# ESP_Clock_v3_1.net
KiCad netlist of a schematic drawn in EAGLE
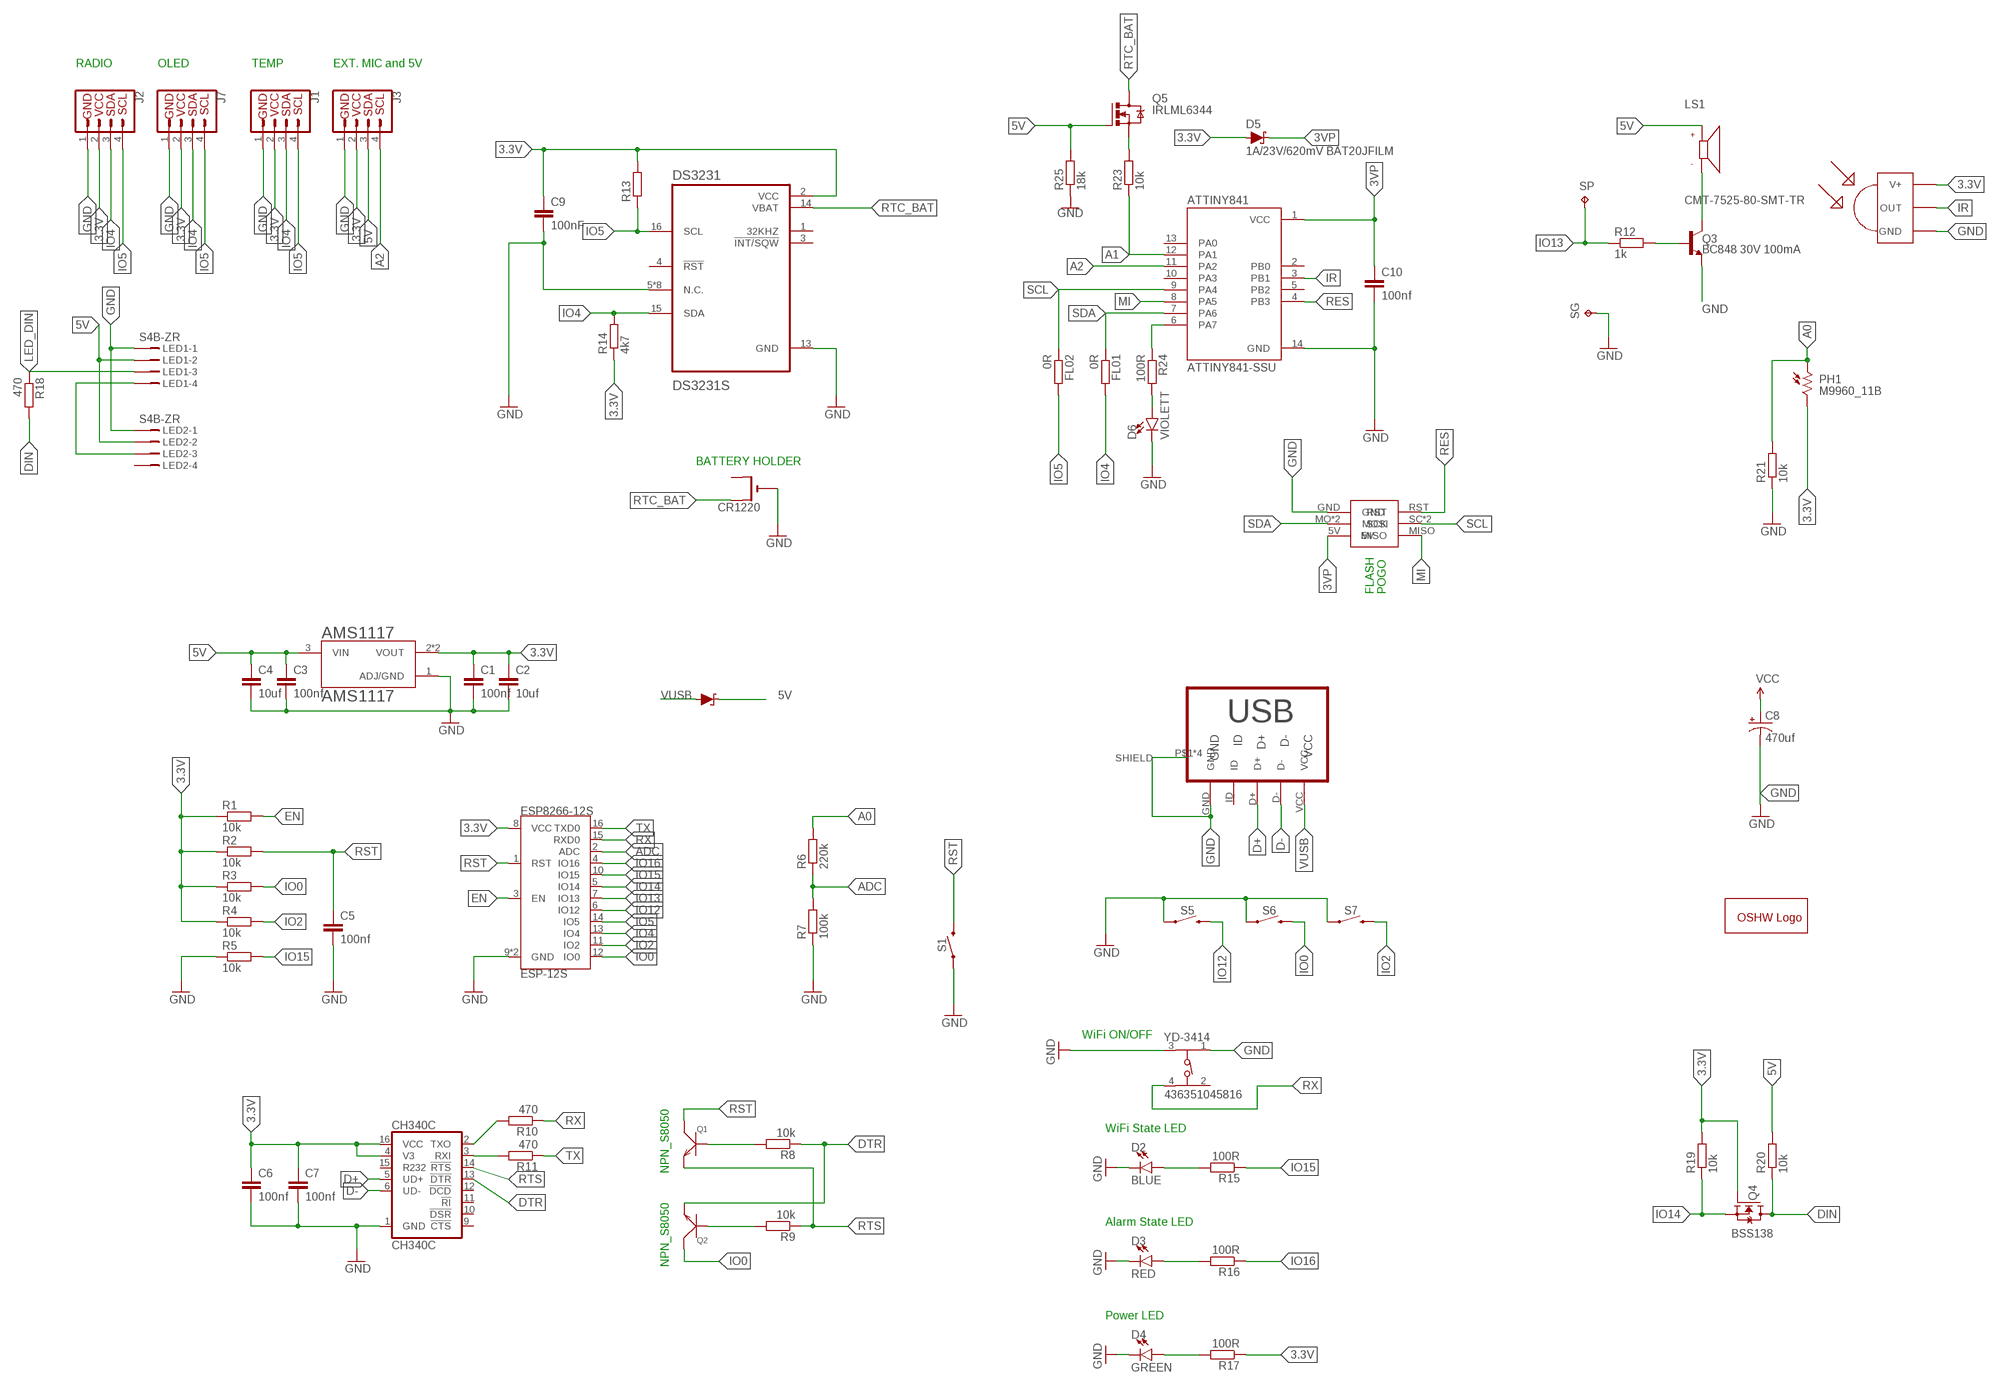
[diagram p0: schematic, sheet 1]

(export (version "E")
  (design (tool "Eeschema 10.0.6"))
  (components
    (comp (ref "AMS1117")
      (value "AMS1117")
      (footprint "eagle-import:SOT229P700X180-4N")
      (fields (field (name "MF") "Advanced Monolithic Systems"))
      (libsource (lib "eagle-import") (part "AMS1117"))
    )
    (comp (ref "ATTINY841")
      (value "ATTINY841-SSU")
      (footprint "eagle-import:SOIC127P599X175-14N")
      (fields (field (name "MF") "Microchip"))
      (libsource (lib "eagle-import") (part "ATTINY841-SSU"))
    )
    (comp (ref "C1")
      (value "100nf")
      (footprint "eagle-import:C0603")
      (libsource (lib "eagle-import") (part "C-EUC0603"))
    )
    (comp (ref "C2")
      (value "10uf")
      (footprint "eagle-import:C0805")
      (libsource (lib "eagle-import") (part "C-EUC0805"))
    )
    (comp (ref "C3")
      (value "100nf")
      (footprint "eagle-import:C0603")
      (libsource (lib "eagle-import") (part "C-EUC0603"))
    )
    (comp (ref "C4")
      (value "10uf")
      (footprint "eagle-import:C0805")
      (libsource (lib "eagle-import") (part "C-EUC0805"))
    )
    (comp (ref "C5")
      (value "100nf")
      (footprint "eagle-import:C0603")
      (libsource (lib "eagle-import") (part "C-EUC0603"))
    )
    (comp (ref "C6")
      (value "100nf")
      (footprint "eagle-import:C0603")
      (libsource (lib "eagle-import") (part "C-EUC0603"))
    )
    (comp (ref "C7")
      (value "100nf")
      (footprint "eagle-import:C0603")
      (libsource (lib "eagle-import") (part "C-EUC0603"))
    )
    (comp (ref "C8")
      (value "470uf")
      (footprint "eagle-import:EIA7343")
      (libsource (lib "eagle-import") (part "CAP_POL7343"))
    )
    (comp (ref "C9")
      (value "100nF")
      (footprint "eagle-import:C0603")
      (libsource (lib "eagle-import") (part "C-EUC0603"))
    )
    (comp (ref "C10")
      (value "100nf")
      (footprint "eagle-import:C0603")
      (libsource (lib "eagle-import") (part "C-EUC0603"))
    )
    (comp (ref "CH340C")
      (value "CH340C")
      (footprint "eagle-import:SO016")
      (fields (field (name "MF") "WCH"))
      (libsource (lib "eagle-import") (part "CH340C"))
    )
    (comp (ref "CR1220")
      (value "CR1220SMT")
      (footprint "eagle-import:CR1220-SMD")
      (libsource (lib "eagle-import") (part "CR1220SMT"))
    )
    (comp (ref "D1")
      (value "MBR130T1G, SL; SOD123 or SMA, 1A")
      (footprint "eagle-import:SMA-DIODE")
      (libsource (lib "eagle-import") (part "DIODE-SCHOTTKY-B340A"))
    )
    (comp (ref "D2")
      (value "BLUE")
      (footprint "eagle-import:LED-0603")
      (libsource (lib "eagle-import") (part "LED-BLUE0603"))
    )
    (comp (ref "D3")
      (value "RED")
      (footprint "eagle-import:LED-0603")
      (libsource (lib "eagle-import") (part "LED-BLUE0603"))
    )
    (comp (ref "D4")
      (value "GREEN")
      (footprint "eagle-import:LED-0603")
      (libsource (lib "eagle-import") (part "LED-BLUE0603"))
    )
    (comp (ref "D5")
      (value "1A/23V/620mV BAT20JFILM")
      (footprint "eagle-import:SOD-323")
      (libsource (lib "eagle-import") (part "DIODE-SCHOTTKY-BAT20J"))
    )
    (comp (ref "D6")
      (value "VIOLETT")
      (footprint "eagle-import:LED-0603")
      (libsource (lib "eagle-import") (part "LED-BLUE0603"))
    )
    (comp (ref "DS3231")
      (value "DS3231S")
      (footprint "eagle-import:SOIC127P1032X265-16N")
      (fields (field (name "MF") "Maxim Integrated"))
      (libsource (lib "eagle-import") (part "DS3231S"))
    )
    (comp (ref "ESP8266-12S")
      (value "ESP-12S")
      (footprint "eagle-import:ESP-12S")
      (fields (field (name "MF") "RF Solutions"))
      (libsource (lib "eagle-import") (part "ESP-12S"))
    )
    (comp (ref "FL01")
      (value "0R")
      (footprint "eagle-import:R0603")
      (libsource (lib "eagle-import") (part "R-EU_R0603"))
    )
    (comp (ref "FL02")
      (value "0R")
      (footprint "eagle-import:R0603")
      (libsource (lib "eagle-import") (part "R-EU_R0603"))
    )
    (comp (ref "GOLD_ORB_SM1")
      (value "OSHWLOGOLOGO5MM")
      (footprint "eagle-import:OSHW_5MM")
      (libsource (lib "eagle-import") (part "OSHWLOGOLOGO5MM"))
    )
    (comp (ref "J1")
      (value "QWIIC_CONNECTORJS-1MM")
      (footprint "eagle-import:1X04_1MM_RA")
      (libsource (lib "eagle-import") (part "QWIIC_CONNECTORJS-1MM"))
    )
    (comp (ref "J2")
      (value "QWIIC_CONNECTORJS-1MM")
      (footprint "eagle-import:1X04_1MM_RA")
      (libsource (lib "eagle-import") (part "QWIIC_CONNECTORJS-1MM"))
    )
    (comp (ref "J3")
      (value "QWIIC_CONNECTORJS-1MM")
      (footprint "eagle-import:1X04_1MM_RA")
      (libsource (lib "eagle-import") (part "QWIIC_CONNECTORJS-1MM"))
    )
    (comp (ref "J7")
      (value "QWIIC_CONNECTORJS-1MM")
      (footprint "eagle-import:1X04_1MM_RA")
      (libsource (lib "eagle-import") (part "QWIIC_CONNECTORJS-1MM"))
    )
    (comp (ref "LED1")
      (value "S4B-ZR")
      (footprint "eagle-import:S4B-ZR")
      (fields (field (name "MF") "FARNELL") (field (name "MPN") "S4B-ZR(LF)(SN)"))
      (libsource (lib "eagle-import") (part "?4B-ZRS"))
    )
    (comp (ref "LED2")
      (value "S4B-ZR")
      (footprint "eagle-import:S4B-ZR")
      (fields (field (name "MF") "FARNELL") (field (name "MPN") "S4B-ZR(LF)(SN)"))
      (libsource (lib "eagle-import") (part "?4B-ZRS"))
    )
    (comp (ref "LS1")
      (value "CMT-7525-80-SMT-TR")
      (footprint "eagle-import:XDCR_CMT-7525-80-SMT-TR")
      (fields (field (name "MF") "CUI Devices"))
      (libsource (lib "eagle-import") (part "CMT-7525-80-SMT-TR"))
    )
    (comp (ref "MICRO-USB")
      (value "MICRO-USB-B")
      (footprint "eagle-import:MICRO_USB_4_LEGS")
      (libsource (lib "eagle-import") (part "MICRO-USB-B"))
    )
    (comp (ref "PH1")
      (value "M9960_11B")
      (footprint "eagle-import:M9960")
      (libsource (lib "eagle-import") (part "M9960_11B"))
    )
    (comp (ref "Q1")
      (value "NPN_S8050")
      (footprint "eagle-import:SOT-23")
      (fields (field (name "MF") "Microdiode Electronics") (field (name "MP") "S8050"))
      (libsource (lib "eagle-import") (part "SMD-TRANSISTORS-NPN-25V-500MW(SOT-23)"))
    )
    (comp (ref "Q2")
      (value "NPN_S8050")
      (footprint "eagle-import:SOT-23")
      (fields (field (name "MF") "Microdiode Electronics") (field (name "MP") "S8050"))
      (libsource (lib "eagle-import") (part "SMD-TRANSISTORS-NPN-25V-500MW(SOT-23)"))
    )
    (comp (ref "Q3")
      (value "BC848 30V 100mA")
      (footprint "eagle-import:SOT23-3")
      (libsource (lib "eagle-import") (part "TRANS_NPN-MMBT2222AL"))
    )
    (comp (ref "Q4")
      (value "BSS138")
      (footprint "eagle-import:SOT95P240X111-3N")
      (fields (field (name "MF") "ON Semiconductor"))
      (libsource (lib "eagle-import") (part "BSS138"))
    )
    (comp (ref "Q5")
      (value "IRLML6344")
      (footprint "eagle-import:SOT23")
      (fields (field (name "MF") "Infineon Technologies"))
      (libsource (lib "eagle-import") (part "IRLML6344"))
    )
    (comp (ref "R1")
      (value "10k")
      (footprint "eagle-import:R0603")
      (libsource (lib "eagle-import") (part "resistor_348_R-EU_R0603"))
    )
    (comp (ref "R2")
      (value "10k")
      (footprint "eagle-import:R0603")
      (libsource (lib "eagle-import") (part "resistor_348_R-EU_R0603"))
    )
    (comp (ref "R3")
      (value "10k")
      (footprint "eagle-import:R0603")
      (libsource (lib "eagle-import") (part "resistor_348_R-EU_R0603"))
    )
    (comp (ref "R4")
      (value "10k")
      (footprint "eagle-import:R0603")
      (libsource (lib "eagle-import") (part "resistor_348_R-EU_R0603"))
    )
    (comp (ref "R5")
      (value "10k")
      (footprint "eagle-import:R0603")
      (libsource (lib "eagle-import") (part "resistor_348_R-EU_R0603"))
    )
    (comp (ref "R6")
      (value "220k")
      (footprint "eagle-import:R0603")
      (libsource (lib "eagle-import") (part "resistor_348_R-EU_R0603"))
    )
    (comp (ref "R7")
      (value "100k")
      (footprint "eagle-import:R0603")
      (libsource (lib "eagle-import") (part "resistor_348_R-EU_R0603"))
    )
    (comp (ref "R8")
      (value "10k")
      (footprint "eagle-import:R0603")
      (libsource (lib "eagle-import") (part "resistor_348_R-EU_R0603"))
    )
    (comp (ref "R9")
      (value "10k")
      (footprint "eagle-import:R0603")
      (libsource (lib "eagle-import") (part "resistor_348_R-EU_R0603"))
    )
    (comp (ref "R10")
      (value "470")
      (footprint "eagle-import:R0603")
      (libsource (lib "eagle-import") (part "resistor_348_R-EU_R0603"))
    )
    (comp (ref "R11")
      (value "470")
      (footprint "eagle-import:R0603")
      (libsource (lib "eagle-import") (part "resistor_348_R-EU_R0603"))
    )
    (comp (ref "R12")
      (value "1k")
      (footprint "eagle-import:R0603")
      (libsource (lib "eagle-import") (part "R-EU_R0603"))
    )
    (comp (ref "R13")
      (value "4k7")
      (footprint "eagle-import:R0603")
      (libsource (lib "eagle-import") (part "resistor_348_R-EU_R0603"))
    )
    (comp (ref "R14")
      (value "4k7")
      (footprint "eagle-import:R0603")
      (libsource (lib "eagle-import") (part "resistor_348_R-EU_R0603"))
    )
    (comp (ref "R15")
      (value "100R")
      (footprint "eagle-import:R0603")
      (libsource (lib "eagle-import") (part "resistor_348_R-EU_R0603"))
    )
    (comp (ref "R16")
      (value "100R")
      (footprint "eagle-import:R0603")
      (libsource (lib "eagle-import") (part "resistor_348_R-EU_R0603"))
    )
    (comp (ref "R17")
      (value "100R")
      (footprint "eagle-import:R0603")
      (libsource (lib "eagle-import") (part "resistor_348_R-EU_R0603"))
    )
    (comp (ref "R18")
      (value "470")
      (footprint "eagle-import:R0603")
      (libsource (lib "eagle-import") (part "resistor_348_R-EU_R0603"))
    )
    (comp (ref "R19")
      (value "10k")
      (footprint "eagle-import:R0603")
      (libsource (lib "eagle-import") (part "resistor_348_R-EU_R0603"))
    )
    (comp (ref "R20")
      (value "10k")
      (footprint "eagle-import:R0603")
      (libsource (lib "eagle-import") (part "resistor_348_R-EU_R0603"))
    )
    (comp (ref "R21")
      (value "10k")
      (footprint "eagle-import:R0603")
      (libsource (lib "eagle-import") (part "R-EU_R0603"))
    )
    (comp (ref "R23")
      (value "10k")
      (footprint "eagle-import:R0603")
      (libsource (lib "eagle-import") (part "R-EU_R0603"))
    )
    (comp (ref "R24")
      (value "100R")
      (footprint "eagle-import:R0603")
      (libsource (lib "eagle-import") (part "R-EU_R0603"))
    )
    (comp (ref "R25")
      (value "18k")
      (footprint "eagle-import:R0603")
      (libsource (lib "eagle-import") (part "resistor_348_R-EU_R0603"))
    )
    (comp (ref "S1")
      (value "MOMENTARY-SWITCH-SPST-SMD-4.6X2.8MM")
      (footprint "eagle-import:TACTILE_SWITCH_SMD_4.6X2.8MM")
      (libsource (lib "eagle-import") (part "MOMENTARY-SWITCH-SPST-SMD-4.6X2.8MM"))
    )
    (comp (ref "S5")
      (value "MOMENTARY-SWITCH-SPST-SMD-4.6X2.8MM")
      (footprint "eagle-import:TACTILE_SWITCH_SMD_4.6X2.8MM")
      (libsource (lib "eagle-import") (part "MOMENTARY-SWITCH-SPST-SMD-4.6X2.8MM"))
    )
    (comp (ref "S6")
      (value "MOMENTARY-SWITCH-SPST-SMD-4.6X2.8MM")
      (footprint "eagle-import:TACTILE_SWITCH_SMD_4.6X2.8MM")
      (libsource (lib "eagle-import") (part "MOMENTARY-SWITCH-SPST-SMD-4.6X2.8MM"))
    )
    (comp (ref "S7")
      (value "MOMENTARY-SWITCH-SPST-SMD-4.6X2.8MM")
      (footprint "eagle-import:TACTILE_SWITCH_SMD_4.6X2.8MM")
      (libsource (lib "eagle-import") (part "MOMENTARY-SWITCH-SPST-SMD-4.6X2.8MM"))
    )
    (comp (ref "SG")
      (value "TPB1,27")
      (footprint "eagle-import:B1,27")
      (libsource (lib "eagle-import") (part "TPB1,27"))
    )
    (comp (ref "SP")
      (value "TPB1,27")
      (footprint "eagle-import:B1,27")
      (libsource (lib "eagle-import") (part "TPB1,27"))
    )
    (comp (ref "U$1")
      (value "ISCP_PORTPOGONEW")
      (footprint "eagle-import:ISCP_PADS_2ROW2HNEW")
      (libsource (lib "eagle-import") (part "ISCP_PORTPOGONEW"))
    )
    (comp (ref "U$2")
      (value "TSOP4838")
      (footprint "eagle-import:TSOP18XX")
      (fields (field (name "MF") "Vishay"))
      (libsource (lib "eagle-import") (part "TSOP4838"))
    )
    (comp (ref "YD-3414")
      (value "436351045816")
      (footprint "eagle-import:4363X10458XX")
      (libsource (lib "eagle-import") (part "436351045816"))
    )
  )
  (nets
    (net (code "1") (name "3.3V") (class "Default")
      (node (ref "AMS1117") (pin "2") (pinfunction "VOUT_2") (pintype "output"))
      (node (ref "AMS1117") (pin "4") (pinfunction "VOUT_4") (pintype "output"))
      (node (ref "C1") (pin "1") (pinfunction "1_1") (pintype "passive"))
      (node (ref "C2") (pin "1") (pinfunction "1_1") (pintype "passive"))
      (node (ref "C6") (pin "1") (pinfunction "1_1") (pintype "passive"))
      (node (ref "C7") (pin "1") (pinfunction "1_1") (pintype "passive"))
      (node (ref "C9") (pin "1") (pinfunction "1_1") (pintype "passive"))
      (node (ref "CH340C") (pin "16") (pinfunction "VCC_16") (pintype "bidirectional"))
      (node (ref "CH340C") (pin "4") (pinfunction "V3_4") (pintype "bidirectional"))
      (node (ref "D5") (pin "A") (pinfunction "A_A") (pintype "passive"))
      (node (ref "DS3231") (pin "2") (pinfunction "VCC_2") (pintype "power_in"))
      (node (ref "ESP8266-12S") (pin "8") (pinfunction "VCC_8") (pintype "bidirectional"))
      (node (ref "J1") (pin "2") (pinfunction "VCC_2") (pintype "power_in"))
      (node (ref "J2") (pin "2") (pinfunction "VCC_2") (pintype "power_in"))
      (node (ref "J3") (pin "2") (pinfunction "VCC_2") (pintype "power_in"))
      (node (ref "J7") (pin "2") (pinfunction "VCC_2") (pintype "power_in"))
      (node (ref "PH1") (pin "2") (pinfunction "2_2") (pintype "passive"))
      (node (ref "Q4") (pin "1") (pinfunction "G_1") (pintype "passive"))
      (node (ref "R1") (pin "1") (pinfunction "1_1") (pintype "passive"))
      (node (ref "R13") (pin "2") (pinfunction "2_2") (pintype "passive"))
      (node (ref "R14") (pin "1") (pinfunction "1_1") (pintype "passive"))
      (node (ref "R17") (pin "1") (pinfunction "1_1") (pintype "passive"))
      (node (ref "R19") (pin "2") (pinfunction "2_2") (pintype "passive"))
      (node (ref "R2") (pin "1") (pinfunction "1_1") (pintype "passive"))
      (node (ref "R3") (pin "1") (pinfunction "1_1") (pintype "passive"))
      (node (ref "R4") (pin "1") (pinfunction "1_1") (pintype "passive"))
      (node (ref "U$2") (pin "VCC") (pinfunction "V+_VCC") (pintype "bidirectional"))
    )
    (net (code "2") (name "3VP") (class "Default")
      (node (ref "ATTINY841") (pin "1") (pinfunction "VCC_1") (pintype "power_in"))
      (node (ref "C10") (pin "1") (pinfunction "1_1") (pintype "passive"))
      (node (ref "D5") (pin "C") (pinfunction "C_C") (pintype "passive"))
      (node (ref "U$1") (pin "5V") (pinfunction "5V_5V") (pintype "bidirectional"))
    )
    (net (code "3") (name "5V") (class "Default")
      (node (ref "AMS1117") (pin "3") (pinfunction "VIN_3") (pintype "input"))
      (node (ref "C3") (pin "1") (pinfunction "1_1") (pintype "passive"))
      (node (ref "C4") (pin "1") (pinfunction "1_1") (pintype "passive"))
      (node (ref "C8") (pin "A") (pinfunction "+_A") (pintype "passive"))
      (node (ref "D1") (pin "C") (pinfunction "C_C") (pintype "passive"))
      (node (ref "J3") (pin "3") (pinfunction "SDA_3") (pintype "passive"))
      (node (ref "LED1") (pin "2") (pinfunction "1_2") (pintype "passive"))
      (node (ref "LED2") (pin "2") (pinfunction "1_2") (pintype "passive"))
      (node (ref "LS1") (pin "P") (pinfunction "P_P") (pintype "passive"))
      (node (ref "Q5") (pin "1") (pinfunction "G_1") (pintype "passive"))
      (node (ref "R20") (pin "2") (pinfunction "2_2") (pintype "passive"))
      (node (ref "R25") (pin "2") (pinfunction "2_2") (pintype "passive"))
    )
    (net (code "4") (name "A0") (class "Default")
      (node (ref "PH1") (pin "1") (pinfunction "1_1") (pintype "passive"))
      (node (ref "R21") (pin "2") (pinfunction "2_2") (pintype "passive"))
      (node (ref "R6") (pin "2") (pinfunction "2_2") (pintype "passive"))
    )
    (net (code "5") (name "A1") (class "Default")
      (node (ref "ATTINY841") (pin "12") (pinfunction "PA1_12") (pintype "bidirectional"))
      (node (ref "R23") (pin "1") (pinfunction "1_1") (pintype "passive"))
    )
    (net (code "6") (name "A2") (class "Default")
      (node (ref "ATTINY841") (pin "11") (pinfunction "PA2_11") (pintype "bidirectional"))
      (node (ref "J3") (pin "4") (pinfunction "SCL_4") (pintype "passive"))
    )
    (net (code "7") (name "ADC") (class "Default")
      (node (ref "ESP8266-12S") (pin "2") (pinfunction "ADC_2") (pintype "bidirectional"))
      (node (ref "R6") (pin "1") (pinfunction "1_1") (pintype "passive"))
      (node (ref "R7") (pin "2") (pinfunction "2_2") (pintype "passive"))
    )
    (net (code "8") (name "D+") (class "Default")
      (node (ref "CH340C") (pin "5") (pinfunction "UD+_5") (pintype "bidirectional"))
      (node (ref "MICRO-USB") (pin "D+") (pinfunction "D+_D+") (pintype "bidirectional"))
    )
    (net (code "9") (name "D-") (class "Default")
      (node (ref "CH340C") (pin "6") (pinfunction "UD-_6") (pintype "bidirectional"))
      (node (ref "MICRO-USB") (pin "D-") (pinfunction "D-_D-") (pintype "bidirectional"))
    )
    (net (code "10") (name "DIN") (class "Default")
      (node (ref "Q4") (pin "3") (pinfunction "D_3") (pintype "passive"))
      (node (ref "R18") (pin "2") (pinfunction "2_2") (pintype "passive"))
      (node (ref "R20") (pin "1") (pinfunction "1_1") (pintype "passive"))
    )
    (net (code "11") (name "DTR") (class "Default")
      (node (ref "CH340C") (pin "13") (pinfunction "~{DTR}_13") (pintype "bidirectional"))
      (node (ref "Q2") (pin "2") (pinfunction "E_2") (pintype "passive"))
      (node (ref "R8") (pin "1") (pinfunction "1_1") (pintype "passive"))
    )
    (net (code "12") (name "EN") (class "Default")
      (node (ref "ESP8266-12S") (pin "3") (pinfunction "EN_3") (pintype "bidirectional"))
      (node (ref "R1") (pin "2") (pinfunction "2_2") (pintype "passive"))
    )
    (net (code "13") (name "GND") (class "Default")
      (node (ref "AMS1117") (pin "1") (pinfunction "ADJ/GND_1") (pintype "power_in"))
      (node (ref "ATTINY841") (pin "14") (pinfunction "GND_14") (pintype "power_in"))
      (node (ref "C1") (pin "2") (pinfunction "2_2") (pintype "passive"))
      (node (ref "C10") (pin "2") (pinfunction "2_2") (pintype "passive"))
      (node (ref "C2") (pin "2") (pinfunction "2_2") (pintype "passive"))
      (node (ref "C3") (pin "2") (pinfunction "2_2") (pintype "passive"))
      (node (ref "C4") (pin "2") (pinfunction "2_2") (pintype "passive"))
      (node (ref "C5") (pin "2") (pinfunction "2_2") (pintype "passive"))
      (node (ref "C6") (pin "2") (pinfunction "2_2") (pintype "passive"))
      (node (ref "C7") (pin "2") (pinfunction "2_2") (pintype "passive"))
      (node (ref "C8") (pin "C") (pinfunction "-_C") (pintype "passive"))
      (node (ref "C9") (pin "2") (pinfunction "2_2") (pintype "passive"))
      (node (ref "CH340C") (pin "1") (pinfunction "GND_1") (pintype "bidirectional"))
      (node (ref "CR1220") (pin "-") (pinfunction "-_-") (pintype "passive"))
      (node (ref "D2") (pin "C") (pinfunction "C_C") (pintype "passive"))
      (node (ref "D3") (pin "C") (pinfunction "C_C") (pintype "passive"))
      (node (ref "D4") (pin "C") (pinfunction "C_C") (pintype "passive"))
      (node (ref "D6") (pin "C") (pinfunction "C_C") (pintype "passive"))
      (node (ref "DS3231") (pin "10") (pinfunction "N.C._10") (pintype "bidirectional"))
      (node (ref "DS3231") (pin "11") (pinfunction "N.C._11") (pintype "bidirectional"))
      (node (ref "DS3231") (pin "12") (pinfunction "N.C._12") (pintype "bidirectional"))
      (node (ref "DS3231") (pin "13") (pinfunction "GND_13") (pintype "power_in"))
      (node (ref "DS3231") (pin "5") (pinfunction "N.C._5") (pintype "bidirectional"))
      (node (ref "DS3231") (pin "6") (pinfunction "N.C._6") (pintype "bidirectional"))
      (node (ref "DS3231") (pin "7") (pinfunction "N.C._7") (pintype "bidirectional"))
      (node (ref "DS3231") (pin "8") (pinfunction "N.C._8") (pintype "bidirectional"))
      (node (ref "DS3231") (pin "9") (pinfunction "N.C._9") (pintype "bidirectional"))
      (node (ref "ESP8266-12S") (pin "9") (pinfunction "GND_9") (pintype "bidirectional"))
      (node (ref "ESP8266-12S") (pin "P$1") (pinfunction "GND_P$1") (pintype "bidirectional"))
      (node (ref "J1") (pin "1") (pinfunction "GND_1") (pintype "power_in"))
      (node (ref "J2") (pin "1") (pinfunction "GND_1") (pintype "power_in"))
      (node (ref "J3") (pin "1") (pinfunction "GND_1") (pintype "power_in"))
      (node (ref "J7") (pin "1") (pinfunction "GND_1") (pintype "power_in"))
      (node (ref "LED1") (pin "1") (pinfunction "1_1") (pintype "passive"))
      (node (ref "LED2") (pin "1") (pinfunction "1_1") (pintype "passive"))
      (node (ref "MICRO-USB") (pin "GND") (pinfunction "GND_GND") (pintype "bidirectional"))
      (node (ref "MICRO-USB") (pin "P$1") (pinfunction "SHIELD_P$1") (pintype "bidirectional"))
      (node (ref "MICRO-USB") (pin "P$2") (pinfunction "SHIELD_P$2") (pintype "bidirectional"))
      (node (ref "MICRO-USB") (pin "P$3") (pinfunction "SHIELD_P$3") (pintype "bidirectional"))
      (node (ref "MICRO-USB") (pin "P$5") (pinfunction "SHIELD_P$5") (pintype "bidirectional"))
      (node (ref "Q3") (pin "2") (pinfunction "E_2") (pintype "passive"))
      (node (ref "R21") (pin "1") (pinfunction "1_1") (pintype "passive"))
      (node (ref "R25") (pin "1") (pinfunction "1_1") (pintype "passive"))
      (node (ref "R5") (pin "1") (pinfunction "1_1") (pintype "passive"))
      (node (ref "R7") (pin "1") (pinfunction "1_1") (pintype "passive"))
      (node (ref "S1") (pin "1") (pinfunction "1_1") (pintype "passive"))
      (node (ref "S1") (pin "2") (pinfunction "1_2") (pintype "passive"))
      (node (ref "S5") (pin "1") (pinfunction "1_1") (pintype "passive"))
      (node (ref "S5") (pin "2") (pinfunction "1_2") (pintype "passive"))
      (node (ref "S6") (pin "1") (pinfunction "1_1") (pintype "passive"))
      (node (ref "S6") (pin "2") (pinfunction "1_2") (pintype "passive"))
      (node (ref "S7") (pin "1") (pinfunction "1_1") (pintype "passive"))
      (node (ref "S7") (pin "2") (pinfunction "1_2") (pintype "passive"))
      (node (ref "SG") (pin "TP") (pinfunction "TP_TP") (pintype "input"))
      (node (ref "U$1") (pin "GND") (pinfunction "GND_GND") (pintype "bidirectional"))
      (node (ref "U$2") (pin "GND") (pinfunction "GND_GND") (pintype "bidirectional"))
      (node (ref "YD-3414") (pin "1") (pinfunction "3_1") (pintype "passive"))
      (node (ref "YD-3414") (pin "3") (pinfunction "1_3") (pintype "passive"))
    )
    (net (code "14") (name "IO0") (class "Default")
      (node (ref "ESP8266-12S") (pin "12") (pinfunction "IO0_12") (pintype "bidirectional"))
      (node (ref "Q2") (pin "3") (pinfunction "C_3") (pintype "passive"))
      (node (ref "R3") (pin "2") (pinfunction "2_2") (pintype "passive"))
      (node (ref "S6") (pin "3") (pinfunction "2_3") (pintype "passive"))
      (node (ref "S6") (pin "4") (pinfunction "2_4") (pintype "passive"))
    )
    (net (code "15") (name "IO2") (class "Default")
      (node (ref "ESP8266-12S") (pin "11") (pinfunction "IO2_11") (pintype "bidirectional"))
      (node (ref "R4") (pin "2") (pinfunction "2_2") (pintype "passive"))
      (node (ref "S7") (pin "3") (pinfunction "2_3") (pintype "passive"))
      (node (ref "S7") (pin "4") (pinfunction "2_4") (pintype "passive"))
    )
    (net (code "16") (name "IO4") (class "Default")
      (node (ref "DS3231") (pin "15") (pinfunction "SDA_15") (pintype "bidirectional"))
      (node (ref "ESP8266-12S") (pin "13") (pinfunction "IO4_13") (pintype "bidirectional"))
      (node (ref "FL01") (pin "2") (pinfunction "2_2") (pintype "passive"))
      (node (ref "J1") (pin "3") (pinfunction "SDA_3") (pintype "passive"))
      (node (ref "J2") (pin "3") (pinfunction "SDA_3") (pintype "passive"))
      (node (ref "J7") (pin "3") (pinfunction "SDA_3") (pintype "passive"))
      (node (ref "R14") (pin "2") (pinfunction "2_2") (pintype "passive"))
    )
    (net (code "17") (name "IO5") (class "Default")
      (node (ref "DS3231") (pin "16") (pinfunction "SCL_16") (pintype "input"))
      (node (ref "ESP8266-12S") (pin "14") (pinfunction "IO5_14") (pintype "bidirectional"))
      (node (ref "FL02") (pin "2") (pinfunction "2_2") (pintype "passive"))
      (node (ref "J1") (pin "4") (pinfunction "SCL_4") (pintype "passive"))
      (node (ref "J2") (pin "4") (pinfunction "SCL_4") (pintype "passive"))
      (node (ref "J7") (pin "4") (pinfunction "SCL_4") (pintype "passive"))
      (node (ref "R13") (pin "1") (pinfunction "1_1") (pintype "passive"))
    )
    (net (code "18") (name "IO12") (class "Default")
      (node (ref "ESP8266-12S") (pin "6") (pinfunction "IO12_6") (pintype "bidirectional"))
      (node (ref "S5") (pin "3") (pinfunction "2_3") (pintype "passive"))
      (node (ref "S5") (pin "4") (pinfunction "2_4") (pintype "passive"))
    )
    (net (code "19") (name "IO13") (class "Default")
      (node (ref "ESP8266-12S") (pin "7") (pinfunction "IO13_7") (pintype "bidirectional"))
      (node (ref "R12") (pin "1") (pinfunction "1_1") (pintype "passive"))
      (node (ref "SP") (pin "TP") (pinfunction "TP_TP") (pintype "input"))
    )
    (net (code "20") (name "IO14") (class "Default")
      (node (ref "ESP8266-12S") (pin "5") (pinfunction "IO14_5") (pintype "bidirectional"))
      (node (ref "Q4") (pin "2") (pinfunction "S_2") (pintype "passive"))
      (node (ref "R19") (pin "1") (pinfunction "1_1") (pintype "passive"))
    )
    (net (code "21") (name "IO15") (class "Default")
      (node (ref "ESP8266-12S") (pin "10") (pinfunction "IO15_10") (pintype "bidirectional"))
      (node (ref "R15") (pin "1") (pinfunction "1_1") (pintype "passive"))
      (node (ref "R5") (pin "2") (pinfunction "2_2") (pintype "passive"))
    )
    (net (code "22") (name "IO16") (class "Default")
      (node (ref "ESP8266-12S") (pin "4") (pinfunction "IO16_4") (pintype "bidirectional"))
      (node (ref "R16") (pin "1") (pinfunction "1_1") (pintype "passive"))
    )
    (net (code "23") (name "IR") (class "Default")
      (node (ref "ATTINY841") (pin "3") (pinfunction "PB1_3") (pintype "bidirectional"))
      (node (ref "U$2") (pin "OUT") (pinfunction "OUT_OUT") (pintype "bidirectional"))
    )
    (net (code "24") (name "LED_DIN") (class "Default")
      (node (ref "LED1") (pin "3") (pinfunction "1_3") (pintype "passive"))
      (node (ref "R18") (pin "1") (pinfunction "1_1") (pintype "passive"))
    )
    (net (code "25") (name "MI") (class "Default")
      (node (ref "ATTINY841") (pin "8") (pinfunction "PA5_8") (pintype "bidirectional"))
      (node (ref "U$1") (pin "MISO") (pinfunction "MISO_MISO") (pintype "bidirectional"))
    )
    (net (code "26") (name "Net-(ATTINY841-PA7)") (class "Default")
      (node (ref "ATTINY841") (pin "6") (pinfunction "PA7_6") (pintype "bidirectional"))
      (node (ref "R24") (pin "1") (pinfunction "1_1") (pintype "passive"))
    )
    (net (code "27") (name "Net-(CH340C-RXI)") (class "Default")
      (node (ref "CH340C") (pin "3") (pinfunction "RXI_3") (pintype "bidirectional"))
      (node (ref "R11") (pin "2") (pinfunction "2_2") (pintype "passive"))
    )
    (net (code "28") (name "Net-(CH340C-TXO)") (class "Default")
      (node (ref "CH340C") (pin "2") (pinfunction "TXO_2") (pintype "bidirectional"))
      (node (ref "R10") (pin "2") (pinfunction "2_2") (pintype "passive"))
    )
    (net (code "29") (name "Net-(D2-PadA)") (class "Default")
      (node (ref "D2") (pin "A") (pinfunction "A_A") (pintype "passive"))
      (node (ref "R15") (pin "2") (pinfunction "2_2") (pintype "passive"))
    )
    (net (code "30") (name "Net-(D3-PadA)") (class "Default")
      (node (ref "D3") (pin "A") (pinfunction "A_A") (pintype "passive"))
      (node (ref "R16") (pin "2") (pinfunction "2_2") (pintype "passive"))
    )
    (net (code "31") (name "Net-(D4-PadA)") (class "Default")
      (node (ref "D4") (pin "A") (pinfunction "A_A") (pintype "passive"))
      (node (ref "R17") (pin "2") (pinfunction "2_2") (pintype "passive"))
    )
    (net (code "32") (name "Net-(D6-PadA)") (class "Default")
      (node (ref "D6") (pin "A") (pinfunction "A_A") (pintype "passive"))
      (node (ref "R24") (pin "2") (pinfunction "2_2") (pintype "passive"))
    )
    (net (code "33") (name "Net-(LED1D-1)") (class "Default")
      (node (ref "LED1") (pin "4") (pinfunction "1_4") (pintype "passive"))
      (node (ref "LED2") (pin "3") (pinfunction "1_3") (pintype "passive"))
    )
    (net (code "34") (name "Net-(Q1-B)") (class "Default")
      (node (ref "Q1") (pin "1") (pinfunction "B_1") (pintype "passive"))
      (node (ref "R8") (pin "2") (pinfunction "2_2") (pintype "passive"))
    )
    (net (code "35") (name "Net-(Q2-B)") (class "Default")
      (node (ref "Q2") (pin "1") (pinfunction "B_1") (pintype "passive"))
      (node (ref "R9") (pin "2") (pinfunction "2_2") (pintype "passive"))
    )
    (net (code "36") (name "Net-(Q3-B)") (class "Default")
      (node (ref "Q3") (pin "1") (pinfunction "B_1") (pintype "passive"))
      (node (ref "R12") (pin "2") (pinfunction "2_2") (pintype "passive"))
    )
    (net (code "37") (name "Net-(Q3-C)") (class "Default")
      (node (ref "LS1") (pin "N") (pinfunction "N_N") (pintype "passive"))
      (node (ref "Q3") (pin "3") (pinfunction "C_3") (pintype "passive"))
    )
    (net (code "38") (name "Net-(Q5-S)") (class "Default")
      (node (ref "Q5") (pin "2") (pinfunction "S_2") (pintype "passive"))
      (node (ref "R23") (pin "2") (pinfunction "2_2") (pintype "passive"))
    )
    (net (code "39") (name "RES") (class "Default")
      (node (ref "ATTINY841") (pin "4") (pinfunction "PB3_4") (pintype "bidirectional"))
      (node (ref "U$1") (pin "RST") (pinfunction "RST_RST") (pintype "bidirectional"))
    )
    (net (code "40") (name "RST") (class "Default")
      (node (ref "C5") (pin "1") (pinfunction "1_1") (pintype "passive"))
      (node (ref "ESP8266-12S") (pin "1") (pinfunction "RST_1") (pintype "bidirectional"))
      (node (ref "Q1") (pin "3") (pinfunction "C_3") (pintype "passive"))
      (node (ref "R2") (pin "2") (pinfunction "2_2") (pintype "passive"))
      (node (ref "S1") (pin "3") (pinfunction "2_3") (pintype "passive"))
      (node (ref "S1") (pin "4") (pinfunction "2_4") (pintype "passive"))
    )
    (net (code "41") (name "RTC_BAT") (class "Default")
      (node (ref "CR1220") (pin "+$1") (pinfunction "+_+$1") (pintype "passive"))
      (node (ref "DS3231") (pin "14") (pinfunction "VBAT_14") (pintype "power_in"))
      (node (ref "Q5") (pin "3") (pinfunction "D_3") (pintype "passive"))
    )
    (net (code "42") (name "RTS") (class "Default")
      (node (ref "CH340C") (pin "14") (pinfunction "~{RTS}_14") (pintype "bidirectional"))
      (node (ref "Q1") (pin "2") (pinfunction "E_2") (pintype "passive"))
      (node (ref "R9") (pin "1") (pinfunction "1_1") (pintype "passive"))
    )
    (net (code "43") (name "RX") (class "Default")
      (node (ref "ESP8266-12S") (pin "15") (pinfunction "RXD0_15") (pintype "bidirectional"))
      (node (ref "R10") (pin "1") (pinfunction "1_1") (pintype "passive"))
      (node (ref "YD-3414") (pin "4") (pinfunction "2_4") (pintype "passive"))
    )
    (net (code "44") (name "SCL") (class "Default")
      (node (ref "ATTINY841") (pin "9") (pinfunction "PA4_9") (pintype "bidirectional"))
      (node (ref "FL02") (pin "1") (pinfunction "1_1") (pintype "passive"))
      (node (ref "U$1") (pin "SC") (pinfunction "SCK_SC") (pintype "bidirectional"))
      (node (ref "U$1") (pin "SCK") (pinfunction "SCK_SCK") (pintype "bidirectional"))
    )
    (net (code "45") (name "SDA") (class "Default")
      (node (ref "ATTINY841") (pin "7") (pinfunction "PA6_7") (pintype "bidirectional"))
      (node (ref "FL01") (pin "1") (pinfunction "1_1") (pintype "passive"))
      (node (ref "U$1") (pin "MO") (pinfunction "MOSI_MO") (pintype "bidirectional"))
      (node (ref "U$1") (pin "MOSI") (pinfunction "MOSI_MOSI") (pintype "bidirectional"))
    )
    (net (code "46") (name "TX") (class "Default")
      (node (ref "ESP8266-12S") (pin "16") (pinfunction "TXD0_16") (pintype "bidirectional"))
      (node (ref "R11") (pin "1") (pinfunction "1_1") (pintype "passive"))
    )
    (net (code "47") (name "VUSB") (class "Default")
      (node (ref "D1") (pin "A") (pinfunction "A_A") (pintype "passive"))
      (node (ref "MICRO-USB") (pin "VCC") (pinfunction "VCC_VCC") (pintype "bidirectional"))
    )
    (net (code "48") (name "unconnected-(ATTINY841-PA0-Pad13)") (class "Default")
      (node (ref "ATTINY841") (pin "13") (pinfunction "PA0_13") (pintype "bidirectional"))
    )
    (net (code "49") (name "unconnected-(ATTINY841-PA3-Pad10)") (class "Default")
      (node (ref "ATTINY841") (pin "10") (pinfunction "PA3_10") (pintype "bidirectional"))
    )
    (net (code "50") (name "unconnected-(ATTINY841-PB0-Pad2)") (class "Default")
      (node (ref "ATTINY841") (pin "2") (pinfunction "PB0_2") (pintype "bidirectional"))
    )
    (net (code "51") (name "unconnected-(ATTINY841-PB2-Pad5)") (class "Default")
      (node (ref "ATTINY841") (pin "5") (pinfunction "PB2_5") (pintype "bidirectional"))
    )
    (net (code "52") (name "unconnected-(CH340C-R232-Pad15)") (class "Default")
      (node (ref "CH340C") (pin "15") (pinfunction "R232_15") (pintype "bidirectional"))
    )
    (net (code "53") (name "unconnected-(CH340C-~{CTS}-Pad9)") (class "Default")
      (node (ref "CH340C") (pin "9") (pinfunction "~{CTS}_9") (pintype "bidirectional"))
    )
    (net (code "54") (name "unconnected-(CH340C-~{DCD}-Pad12)") (class "Default")
      (node (ref "CH340C") (pin "12") (pinfunction "~{DCD}_12") (pintype "bidirectional"))
    )
    (net (code "55") (name "unconnected-(CH340C-~{DSR}-Pad10)") (class "Default")
      (node (ref "CH340C") (pin "10") (pinfunction "~{DSR}_10") (pintype "bidirectional"))
    )
    (net (code "56") (name "unconnected-(CH340C-~{RI}-Pad11)") (class "Default")
      (node (ref "CH340C") (pin "11") (pinfunction "~{RI}_11") (pintype "bidirectional"))
    )
    (net (code "57") (name "unconnected-(CR1220-+1-Pad+$2)") (class "Default")
      (node (ref "CR1220") (pin "+$2") (pinfunction "+1_+$2") (pintype "passive"))
    )
    (net (code "58") (name "unconnected-(DS3231-32KHZ-Pad1)") (class "Default")
      (node (ref "DS3231") (pin "1") (pinfunction "32KHZ_1") (pintype "output"))
    )
    (net (code "59") (name "unconnected-(DS3231-~{INT{slash}SQW}-Pad3)") (class "Default")
      (node (ref "DS3231") (pin "3") (pinfunction "~{INT/SQW}_3") (pintype "output"))
    )
    (net (code "60") (name "unconnected-(DS3231-~{RST}-Pad4)") (class "Default")
      (node (ref "DS3231") (pin "4") (pinfunction "~{RST}_4") (pintype "bidirectional"))
    )
    (net (code "61") (name "unconnected-(LED2D-1-Pad4)") (class "Default")
      (node (ref "LED2") (pin "4") (pinfunction "1_4") (pintype "passive"))
    )
    (net (code "62") (name "unconnected-(MICRO-USB-PadID)") (class "Default")
      (node (ref "MICRO-USB") (pin "ID") (pinfunction "ID_ID") (pintype "bidirectional"))
    )
    (net (code "63") (name "unconnected-(YD-3414-4-Pad2)") (class "Default")
      (node (ref "YD-3414") (pin "2") (pinfunction "4_2") (pintype "passive"))
    )
  )
)
